# 3V_ADC_SUPPLY.net
KiCad netlist of a schematic drawn in Altium Designer
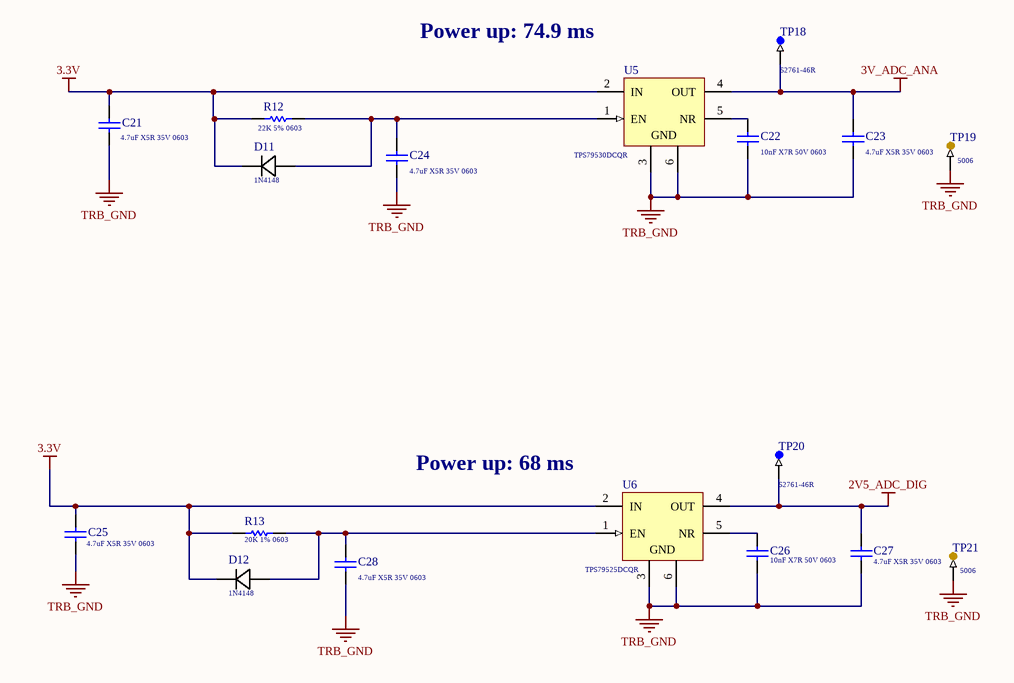
[diagram p0: 3V_ADC_SUPPLY.SchDoc]

(export (version "E")
  (design (tool "Eeschema 10.0.6"))
  (components
    (comp (ref "C21")
      (value "Cap_Murata_ZRB18AR6YA475ME05L_4.7uF")
      (footprint "Cap_Murata_ZRB18AR6YA475ME05L_4.7uF")
      (description "CAP CER 4.7uF 35V X5R 0603")
      (fields (field (name "CAPACITANCE") "4.7uF X5R 35V 0603"))
      (libsource (lib "Cap_Murata_ZRB18AR6YA475ME05L_4.7uF") (part "Cap_Murata_ZRB18AR6YA475ME05L_4.7uF"))
    )
    (comp (ref "C22")
      (value "Cap_Kemet_C0603C103J5RACTU_eec")
      (footprint "Kemet_C0603_0")
      (description "CAP CER 10nF 50V X7R 0603")
      (fields
        (field (name "PART NUMBER") "C0603C103J5RACTU")
        (field (name "MANUFACTURER") "Kemet")
        (field (name "CAPACITANCE") "10nF X7R 50V 0603")
      )
      (libsource (lib "Cap_Kemet_C0603C103J5RACTU_10nF") (part "Cap_Kemet_C0603C103J5RACTU_eec"))
    )
    (comp (ref "C23")
      (value "Cap_Murata_ZRB18AR6YA475ME05L_4.7uF")
      (footprint "Cap_Murata_ZRB18AR6YA475ME05L_4.7uF")
      (description "CAP CER 4.7uF 35V X5R 0603")
      (fields (field (name "CAPACITANCE") "4.7uF X5R 35V 0603"))
      (libsource (lib "Cap_Murata_ZRB18AR6YA475ME05L_4.7uF") (part "Cap_Murata_ZRB18AR6YA475ME05L_4.7uF"))
    )
    (comp (ref "C24")
      (value "Cap_Murata_ZRB18AR6YA475ME05L_4.7uF")
      (footprint "Cap_Murata_ZRB18AR6YA475ME05L_4.7uF")
      (description "CAP CER 4.7uF 35V X5R 0603")
      (fields (field (name "CAPACITANCE") "4.7uF X5R 35V 0603"))
      (libsource (lib "Cap_Murata_ZRB18AR6YA475ME05L_4.7uF") (part "Cap_Murata_ZRB18AR6YA475ME05L_4.7uF"))
    )
    (comp (ref "C25")
      (value "Cap_Murata_ZRB18AR6YA475ME05L_4.7uF")
      (footprint "Cap_Murata_ZRB18AR6YA475ME05L_4.7uF")
      (description "CAP CER 4.7uF 35V X5R 0603")
      (fields (field (name "CAPACITANCE") "4.7uF X5R 35V 0603"))
      (libsource (lib "Cap_Murata_ZRB18AR6YA475ME05L_4.7uF") (part "Cap_Murata_ZRB18AR6YA475ME05L_4.7uF"))
    )
    (comp (ref "C26")
      (value "Cap_Kemet_C0603C103J5RACTU_eec")
      (footprint "Kemet_C0603_0")
      (description "CAP CER 10nF 50V X7R 0603")
      (fields
        (field (name "PART NUMBER") "C0603C103J5RACTU")
        (field (name "MANUFACTURER") "Kemet")
        (field (name "CAPACITANCE") "10nF X7R 50V 0603")
      )
      (libsource (lib "Cap_Kemet_C0603C103J5RACTU_10nF") (part "Cap_Kemet_C0603C103J5RACTU_eec"))
    )
    (comp (ref "C27")
      (value "Cap_Murata_ZRB18AR6YA475ME05L_4.7uF")
      (footprint "Cap_Murata_ZRB18AR6YA475ME05L_4.7uF")
      (description "CAP CER 4.7uF 35V X5R 0603")
      (fields (field (name "CAPACITANCE") "4.7uF X5R 35V 0603"))
      (libsource (lib "Cap_Murata_ZRB18AR6YA475ME05L_4.7uF") (part "Cap_Murata_ZRB18AR6YA475ME05L_4.7uF"))
    )
    (comp (ref "C28")
      (value "Cap_Murata_ZRB18AR6YA475ME05L_4.7uF")
      (footprint "Cap_Murata_ZRB18AR6YA475ME05L_4.7uF")
      (description "CAP CER 4.7uF 35V X5R 0603")
      (fields (field (name "CAPACITANCE") "4.7uF X5R 35V 0603"))
      (libsource (lib "Cap_Murata_ZRB18AR6YA475ME05L_4.7uF") (part "Cap_Murata_ZRB18AR6YA475ME05L_4.7uF"))
    )
    (comp (ref "D11")
      (value "Diode_ON_Semiconductor_1N4148WT_300mA")
      (footprint "Diode_ON_Semiconductor_1N4148WT_300mA")
      (description "Diodes - General Purpose, Power, Switching SINGLE JUNC. 75V 4.0NS COMP")
      (fields (field (name "SERIES") "1N4148"))
      (libsource (lib "Diode_ON_Semiconductor_1N4148WT_300mA") (part "Diode_ON_Semiconductor_1N4148WT_300mA"))
    )
    (comp (ref "D12")
      (value "Diode_ON_Semiconductor_1N4148WT_300mA")
      (footprint "Diode_ON_Semiconductor_1N4148WT_300mA")
      (description "Diodes - General Purpose, Power, Switching SINGLE JUNC. 75V 4.0NS COMP")
      (fields (field (name "SERIES") "1N4148"))
      (libsource (lib "Diode_ON_Semiconductor_1N4148WT_300mA") (part "Diode_ON_Semiconductor_1N4148WT_300mA"))
    )
    (comp (ref "R12")
      (value "22K 5% 0603")
      (footprint "RESC0603(1608)_L")
      (description "22K 0.1W 5% 0603 (1608 Metric)  SMD")
      (fields (field (name "POWER") "0.1 W") (field (name "TOLERANCE") "5 %"))
      (libsource (lib "Altium Content Vault") (part "RES"))
    )
    (comp (ref "R13")
      (value "20K 1% 0603")
      (footprint "RESC0603(1608)_L")
      (description "20K 0.1W 1% 0603 (1608 Metric)  SMD")
      (fields (field (name "TOLERANCE") "1 %") (field (name "POWER") "0.1 W"))
      (libsource (lib "Altium Content Vault") (part "RES"))
    )
    (comp (ref "TP18")
      (value "TP_Harwin_S2761_46R")
      (footprint "TP_Harwin_S2761_46R")
      (description "Circuit Board Hardware - PCB SMT Mini Test Terminal, Reel")
      (fields (field (name "SERIES") "S2761-46R"))
      (libsource (lib "TP_Harwin_S2761_46R") (part "TP_Harwin_S2761_46R"))
    )
    (comp (ref "TP19")
      (value "TP_Keystone_Electronics_5006")
      (footprint "TP_Keystone_Electronics_5006")
      (description "Circuit Board Hardware - PCB TEST POINT BLK .063")
      (fields (field (name "SERIES") "5006"))
      (libsource (lib "TP_Keystone_Electronics_5006") (part "TP_Keystone_Electronics_5006"))
    )
    (comp (ref "TP20")
      (value "TP_Harwin_S2761_46R")
      (footprint "TP_Harwin_S2761_46R")
      (description "Circuit Board Hardware - PCB SMT Mini Test Terminal, Reel")
      (fields (field (name "SERIES") "S2761-46R"))
      (libsource (lib "TP_Harwin_S2761_46R") (part "TP_Harwin_S2761_46R"))
    )
    (comp (ref "TP21")
      (value "TP_Keystone_Electronics_5006")
      (footprint "TP_Keystone_Electronics_5006")
      (description "Circuit Board Hardware - PCB TEST POINT BLK .063")
      (fields (field (name "SERIES") "5006"))
      (libsource (lib "TP_Keystone_Electronics_5006") (part "TP_Keystone_Electronics_5006"))
    )
    (comp (ref "U5")
      (value "TPS79530DCQR")
      (footprint "TI-DCQ6_N")
      (fields (field (name "MANUFACTURER") "Texas Instruments"))
      (libsource (lib "IC_Texas_Instruments_TPS79530DCQR") (part "TPS79530DCQR"))
    )
    (comp (ref "U6")
      (value "TPS79525DCQR")
      (footprint "DCQ0006A_N")
      (fields (field (name "MANUFACTURER") "Texas Instruments"))
      (libsource (lib "IC_Texas Instruments_TPS79525DCQR") (part "TPS79525DCQR"))
    )
  )
  (nets
    (net (code "1") (name "2V5_ADC_DIG") (class "Default")
      (node (ref "C27") (pin "2") (pinfunction "2_2") (pintype "passive"))
      (node (ref "TP20") (pin "1") (pinfunction "1_1") (pintype "input"))
      (node (ref "U6") (pin "4") (pinfunction "OUT_4") (pintype "power_in"))
    )
    (net (code "2") (name "3.3V") (class "Default")
      (node (ref "C21") (pin "2") (pinfunction "2_2") (pintype "passive"))
      (node (ref "C25") (pin "2") (pinfunction "2_2") (pintype "passive"))
      (node (ref "D11") (pin "1") (pinfunction "1_1") (pintype "passive"))
      (node (ref "D12") (pin "1") (pinfunction "1_1") (pintype "passive"))
      (node (ref "R12") (pin "1") (pinfunction "1_1") (pintype "passive"))
      (node (ref "R13") (pin "2") (pinfunction "2_2") (pintype "passive"))
      (node (ref "U5") (pin "2") (pinfunction "IN_2") (pintype "power_in"))
      (node (ref "U6") (pin "2") (pinfunction "IN_2") (pintype "power_in"))
    )
    (net (code "3") (name "3V_ADC_ANA") (class "Default")
      (node (ref "C23") (pin "2") (pinfunction "2_2") (pintype "passive"))
      (node (ref "TP18") (pin "1") (pinfunction "1_1") (pintype "input"))
      (node (ref "U5") (pin "4") (pinfunction "OUT_4") (pintype "power_in"))
    )
    (net (code "4") (name "Net-(U5-EN)") (class "Default")
      (node (ref "C24") (pin "2") (pinfunction "2_2") (pintype "passive"))
      (node (ref "D11") (pin "2") (pinfunction "2_2") (pintype "passive"))
      (node (ref "R12") (pin "2") (pinfunction "2_2") (pintype "passive"))
      (node (ref "U5") (pin "1") (pinfunction "EN_1") (pintype "input"))
    )
    (net (code "5") (name "Net-(U5-NR)") (class "Default")
      (node (ref "C22") (pin "1") (pinfunction "1_1") (pintype "passive"))
      (node (ref "U5") (pin "5") (pinfunction "NR_5") (pintype "passive"))
    )
    (net (code "6") (name "Net-(U6-EN)") (class "Default")
      (node (ref "C28") (pin "2") (pinfunction "2_2") (pintype "passive"))
      (node (ref "D12") (pin "2") (pinfunction "2_2") (pintype "passive"))
      (node (ref "R13") (pin "1") (pinfunction "1_1") (pintype "passive"))
      (node (ref "U6") (pin "1") (pinfunction "EN_1") (pintype "input"))
    )
    (net (code "7") (name "Net-(U6-NR)") (class "Default")
      (node (ref "C26") (pin "1") (pinfunction "1_1") (pintype "passive"))
      (node (ref "U6") (pin "5") (pinfunction "NR_5") (pintype "passive"))
    )
    (net (code "8") (name "TRB_GND") (class "Default")
      (node (ref "C21") (pin "1") (pinfunction "1_1") (pintype "passive"))
      (node (ref "C22") (pin "2") (pinfunction "2_2") (pintype "passive"))
      (node (ref "C23") (pin "1") (pinfunction "1_1") (pintype "passive"))
      (node (ref "C24") (pin "1") (pinfunction "1_1") (pintype "passive"))
      (node (ref "C25") (pin "1") (pinfunction "1_1") (pintype "passive"))
      (node (ref "C26") (pin "2") (pinfunction "2_2") (pintype "passive"))
      (node (ref "C27") (pin "1") (pinfunction "1_1") (pintype "passive"))
      (node (ref "C28") (pin "1") (pinfunction "1_1") (pintype "passive"))
      (node (ref "TP19") (pin "1") (pinfunction "1_1") (pintype "input"))
      (node (ref "TP21") (pin "1") (pinfunction "1_1") (pintype "input"))
      (node (ref "U5") (pin "3") (pinfunction "GND_3") (pintype "power_in"))
      (node (ref "U5") (pin "6") (pinfunction "GND_6") (pintype "power_in"))
      (node (ref "U6") (pin "3") (pinfunction "GND_3") (pintype "power_in"))
      (node (ref "U6") (pin "6") (pinfunction "GND_6") (pintype "power_in"))
    )
  )
)
